# BigClown_Sensor_adapter_v0_1.net
KiCad netlist of a schematic drawn in EAGLE
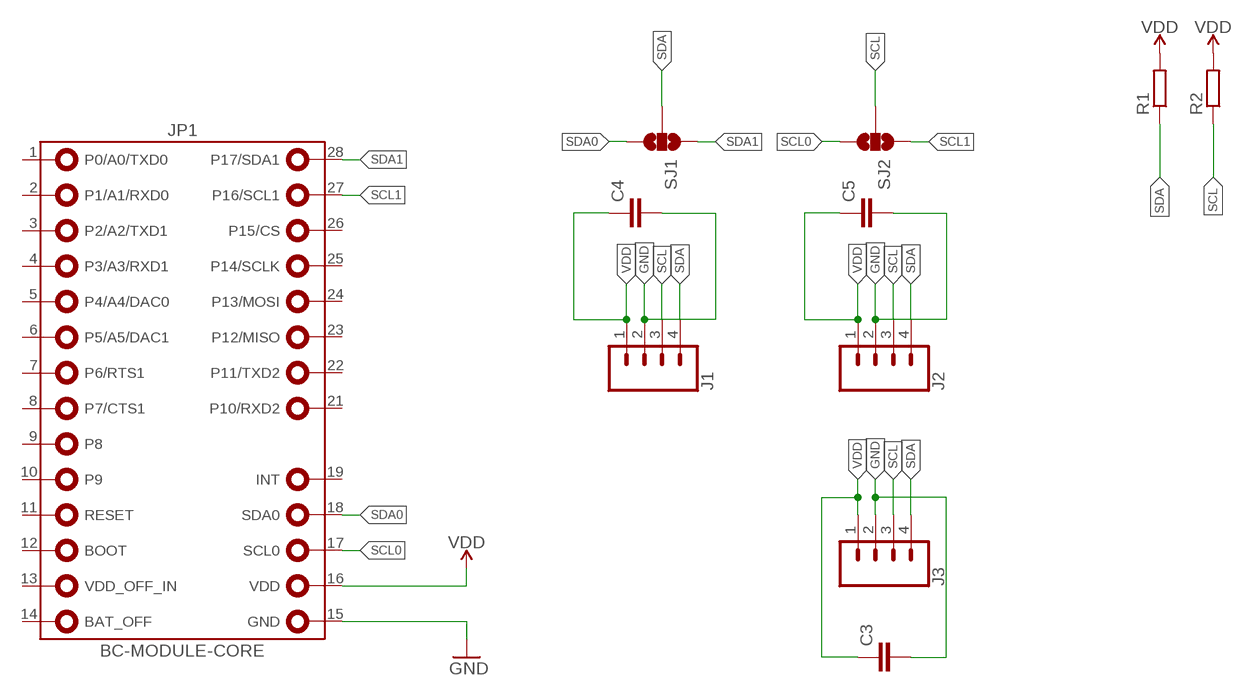
[diagram p0: schematic, sheet 1]

(export (version "E")
  (design (tool "Eeschema 10.0.6"))
  (components
    (comp (ref "C3")
      (value "C-EUC0805")
      (footprint "eagle-import:C0805")
      (libsource (lib "eagle-import") (part "C-EUC0805"))
    )
    (comp (ref "C4")
      (value "C-EUC0805")
      (footprint "eagle-import:C0805")
      (libsource (lib "eagle-import") (part "C-EUC0805"))
    )
    (comp (ref "C5")
      (value "C-EUC0805")
      (footprint "eagle-import:C0805")
      (libsource (lib "eagle-import") (part "C-EUC0805"))
    )
    (comp (ref "J1")
      (value "CONN_04LONGPADS")
      (footprint "eagle-import:1X04_LONGPADS")
      (libsource (lib "eagle-import") (part "CONN_04LONGPADS"))
    )
    (comp (ref "J2")
      (value "CONN_04LONGPADS")
      (footprint "eagle-import:1X04_LONGPADS")
      (libsource (lib "eagle-import") (part "CONN_04LONGPADS"))
    )
    (comp (ref "J3")
      (value "CONN_04LONGPADS")
      (footprint "eagle-import:1X04_LONGPADS")
      (libsource (lib "eagle-import") (part "CONN_04LONGPADS"))
    )
    (comp (ref "JP1")
      (value "BC-MODULE-CORE")
      (footprint "eagle-import:BC-MODULE-CORE")
      (libsource (lib "eagle-import") (part "BC-MODULE-CORE"))
    )
    (comp (ref "R1")
      (value "R-EU_M0805")
      (footprint "eagle-import:M0805")
      (libsource (lib "eagle-import") (part "R-EU_M0805"))
    )
    (comp (ref "R2")
      (value "R-EU_M0805")
      (footprint "eagle-import:M0805")
      (libsource (lib "eagle-import") (part "R-EU_M0805"))
    )
    (comp (ref "SJ1")
      (value "SOLDERJUMPER_2WAYS")
      (footprint "eagle-import:SJ_3")
      (libsource (lib "eagle-import") (part "SOLDERJUMPER_2WAYS"))
    )
    (comp (ref "SJ2")
      (value "SOLDERJUMPER_2WAYS")
      (footprint "eagle-import:SJ_3")
      (libsource (lib "eagle-import") (part "SOLDERJUMPER_2WAYS"))
    )
  )
  (nets
    (net (code "1") (name "GND") (class "Default")
      (node (ref "C3") (pin "2") (pinfunction "2_2") (pintype "passive"))
      (node (ref "C4") (pin "2") (pinfunction "2_2") (pintype "passive"))
      (node (ref "C5") (pin "2") (pinfunction "2_2") (pintype "passive"))
      (node (ref "J1") (pin "2") (pinfunction "2_2") (pintype "passive"))
      (node (ref "J2") (pin "2") (pinfunction "2_2") (pintype "passive"))
      (node (ref "J3") (pin "2") (pinfunction "2_2") (pintype "passive"))
      (node (ref "JP1") (pin "15") (pinfunction "GND_15") (pintype "passive"))
    )
    (net (code "2") (name "SCL") (class "Default")
      (node (ref "J1") (pin "3") (pinfunction "3_3") (pintype "passive"))
      (node (ref "J2") (pin "3") (pinfunction "3_3") (pintype "passive"))
      (node (ref "J3") (pin "3") (pinfunction "3_3") (pintype "passive"))
      (node (ref "R2") (pin "1") (pinfunction "1_1") (pintype "passive"))
      (node (ref "SJ2") (pin "2") (pinfunction "2_2") (pintype "passive"))
    )
    (net (code "3") (name "SCL0") (class "Default")
      (node (ref "JP1") (pin "17") (pinfunction "SCL0_17") (pintype "passive"))
      (node (ref "SJ2") (pin "3") (pinfunction "3_3") (pintype "passive"))
    )
    (net (code "4") (name "SCL1") (class "Default")
      (node (ref "JP1") (pin "27") (pinfunction "P16/SCL1_27") (pintype "passive"))
      (node (ref "SJ2") (pin "1") (pinfunction "1_1") (pintype "passive"))
    )
    (net (code "5") (name "SDA") (class "Default")
      (node (ref "J1") (pin "4") (pinfunction "4_4") (pintype "passive"))
      (node (ref "J2") (pin "4") (pinfunction "4_4") (pintype "passive"))
      (node (ref "J3") (pin "4") (pinfunction "4_4") (pintype "passive"))
      (node (ref "R1") (pin "1") (pinfunction "1_1") (pintype "passive"))
      (node (ref "SJ1") (pin "2") (pinfunction "2_2") (pintype "passive"))
    )
    (net (code "6") (name "SDA0") (class "Default")
      (node (ref "JP1") (pin "18") (pinfunction "SDA0_18") (pintype "passive"))
      (node (ref "SJ1") (pin "3") (pinfunction "3_3") (pintype "passive"))
    )
    (net (code "7") (name "SDA1") (class "Default")
      (node (ref "JP1") (pin "28") (pinfunction "P17/SDA1_28") (pintype "passive"))
      (node (ref "SJ1") (pin "1") (pinfunction "1_1") (pintype "passive"))
    )
    (net (code "8") (name "VDD") (class "Default")
      (node (ref "C3") (pin "1") (pinfunction "1_1") (pintype "passive"))
      (node (ref "C4") (pin "1") (pinfunction "1_1") (pintype "passive"))
      (node (ref "C5") (pin "1") (pinfunction "1_1") (pintype "passive"))
      (node (ref "J1") (pin "1") (pinfunction "1_1") (pintype "passive"))
      (node (ref "J2") (pin "1") (pinfunction "1_1") (pintype "passive"))
      (node (ref "J3") (pin "1") (pinfunction "1_1") (pintype "passive"))
      (node (ref "JP1") (pin "16") (pinfunction "VDD_16") (pintype "passive"))
      (node (ref "R1") (pin "2") (pinfunction "2_2") (pintype "passive"))
      (node (ref "R2") (pin "2") (pinfunction "2_2") (pintype "passive"))
    )
    (net (code "9") (name "unconnected-(JP1-BAT_OFF-Pad14)") (class "Default")
      (node (ref "JP1") (pin "14") (pinfunction "BAT_OFF_14") (pintype "passive"))
    )
    (net (code "10") (name "unconnected-(JP1-BOOT-Pad12)") (class "Default")
      (node (ref "JP1") (pin "12") (pinfunction "BOOT_12") (pintype "passive"))
    )
    (net (code "11") (name "unconnected-(JP1-INT-Pad19)") (class "Default")
      (node (ref "JP1") (pin "19") (pinfunction "INT_19") (pintype "passive"))
    )
    (net (code "12") (name "unconnected-(JP1-P0{slash}A0{slash}TXD0-Pad1)") (class "Default")
      (node (ref "JP1") (pin "1") (pinfunction "P0/A0/TXD0_1") (pintype "passive"))
    )
    (net (code "13") (name "unconnected-(JP1-P1{slash}A1{slash}RXD0-Pad2)") (class "Default")
      (node (ref "JP1") (pin "2") (pinfunction "P1/A1/RXD0_2") (pintype "passive"))
    )
    (net (code "14") (name "unconnected-(JP1-P2{slash}A2{slash}TXD1-Pad3)") (class "Default")
      (node (ref "JP1") (pin "3") (pinfunction "P2/A2/TXD1_3") (pintype "passive"))
    )
    (net (code "15") (name "unconnected-(JP1-P3{slash}A3{slash}RXD1-Pad4)") (class "Default")
      (node (ref "JP1") (pin "4") (pinfunction "P3/A3/RXD1_4") (pintype "passive"))
    )
    (net (code "16") (name "unconnected-(JP1-P4{slash}A4{slash}DAC0-Pad5)") (class "Default")
      (node (ref "JP1") (pin "5") (pinfunction "P4/A4/DAC0_5") (pintype "passive"))
    )
    (net (code "17") (name "unconnected-(JP1-P5{slash}A5{slash}DAC1-Pad6)") (class "Default")
      (node (ref "JP1") (pin "6") (pinfunction "P5/A5/DAC1_6") (pintype "passive"))
    )
    (net (code "18") (name "unconnected-(JP1-P6{slash}RTS1-Pad7)") (class "Default")
      (node (ref "JP1") (pin "7") (pinfunction "P6/RTS1_7") (pintype "passive"))
    )
    (net (code "19") (name "unconnected-(JP1-P7{slash}CTS1-Pad8)") (class "Default")
      (node (ref "JP1") (pin "8") (pinfunction "P7/CTS1_8") (pintype "passive"))
    )
    (net (code "20") (name "unconnected-(JP1-P8-Pad9)") (class "Default")
      (node (ref "JP1") (pin "9") (pinfunction "P8_9") (pintype "passive"))
    )
    (net (code "21") (name "unconnected-(JP1-P9-Pad10)") (class "Default")
      (node (ref "JP1") (pin "10") (pinfunction "P9_10") (pintype "passive"))
    )
    (net (code "22") (name "unconnected-(JP1-P10{slash}RXD2-Pad21)") (class "Default")
      (node (ref "JP1") (pin "21") (pinfunction "P10/RXD2_21") (pintype "passive"))
    )
    (net (code "23") (name "unconnected-(JP1-P11{slash}TXD2-Pad22)") (class "Default")
      (node (ref "JP1") (pin "22") (pinfunction "P11/TXD2_22") (pintype "passive"))
    )
    (net (code "24") (name "unconnected-(JP1-P12{slash}MISO-Pad23)") (class "Default")
      (node (ref "JP1") (pin "23") (pinfunction "P12/MISO_23") (pintype "passive"))
    )
    (net (code "25") (name "unconnected-(JP1-P13{slash}MOSI-Pad24)") (class "Default")
      (node (ref "JP1") (pin "24") (pinfunction "P13/MOSI_24") (pintype "passive"))
    )
    (net (code "26") (name "unconnected-(JP1-P14{slash}SCLK-Pad25)") (class "Default")
      (node (ref "JP1") (pin "25") (pinfunction "P14/SCLK_25") (pintype "passive"))
    )
    (net (code "27") (name "unconnected-(JP1-P15{slash}CS-Pad26)") (class "Default")
      (node (ref "JP1") (pin "26") (pinfunction "P15/CS_26") (pintype "passive"))
    )
    (net (code "28") (name "unconnected-(JP1-RESET-Pad11)") (class "Default")
      (node (ref "JP1") (pin "11") (pinfunction "RESET_11") (pintype "passive"))
    )
    (net (code "29") (name "unconnected-(JP1-VDD_OFF_IN-Pad13)") (class "Default")
      (node (ref "JP1") (pin "13") (pinfunction "VDD_OFF_IN_13") (pintype "passive"))
    )
  )
)
